# sensorCO2LinearSupply.net
KiCad netlist of a schematic drawn in EAGLE
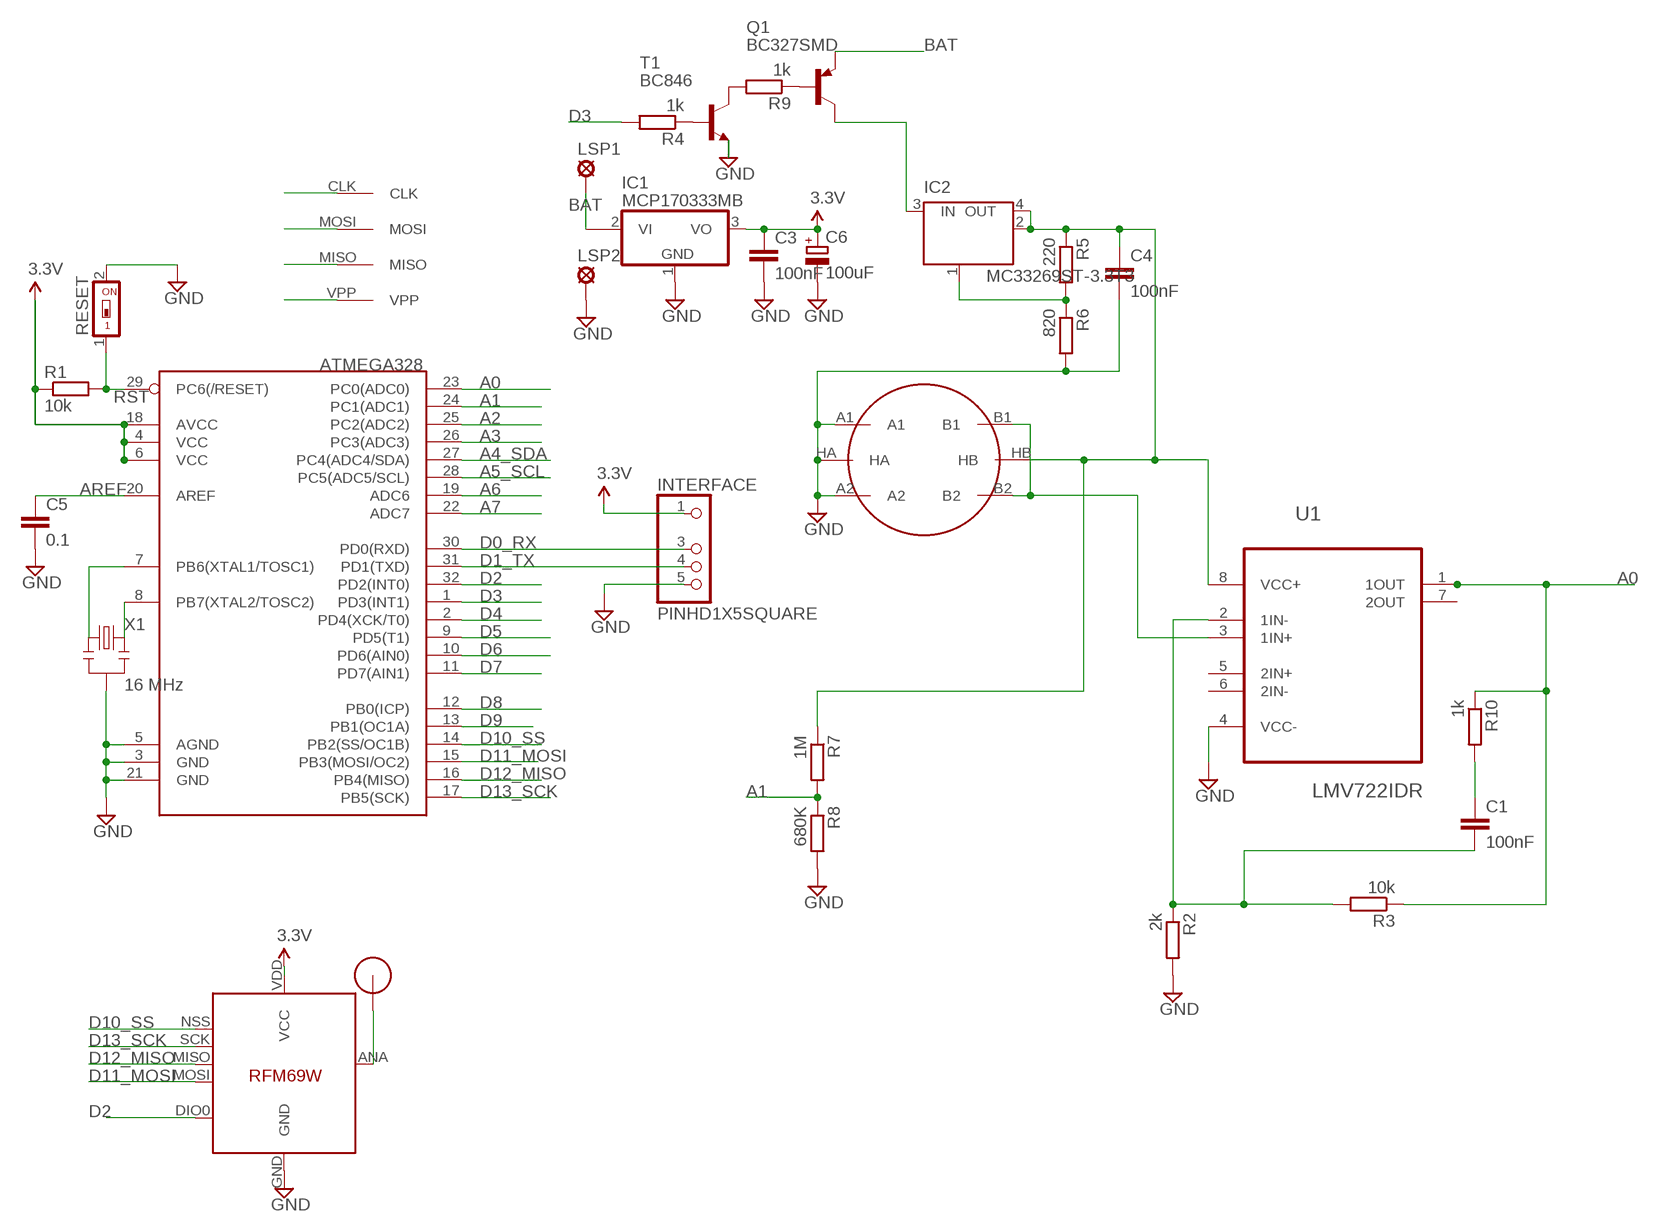
[diagram p0: schematic, sheet 1]

(export (version "E")
  (design (tool "Eeschema 10.0.6"))
  (components
    (comp (ref "ATMEGA328")
      (value "ATMega-328")
      (footprint "eagle-import:TQFP32-08")
      (libsource (lib "eagle-import") (part "ATMEGA168/328TQFP32"))
    )
    (comp (ref "C1")
      (value "100nF")
      (footprint "eagle-import:C2012")
      (libsource (lib "eagle-import") (part "C-EUC2012"))
    )
    (comp (ref "C3")
      (value "100nF")
      (footprint "eagle-import:C2012")
      (libsource (lib "eagle-import") (part "C-EUC2012"))
    )
    (comp (ref "C4")
      (value "100nF")
      (footprint "eagle-import:C2012")
      (libsource (lib "eagle-import") (part "C-EUC2012"))
    )
    (comp (ref "C5")
      (value "0.1")
      (footprint "eagle-import:C2012")
      (libsource (lib "eagle-import") (part "C-EUC2012"))
    )
    (comp (ref "C6")
      (value "100uF")
      (footprint "eagle-import:SMC_B")
      (libsource (lib "eagle-import") (part "CPOL-EUSMCB"))
    )
    (comp (ref "IC1")
      (value "MCP170333MB")
      (footprint "eagle-import:SOT89")
      (libsource (lib "eagle-import") (part "MCP1703MB33"))
    )
    (comp (ref "IC2")
      (value "MC33269ST-3.3T3")
      (footprint "eagle-import:SOT223")
      (libsource (lib "eagle-import") (part "MC33269ST-3.3T3"))
    )
    (comp (ref "IC4")
      (value "RFM69")
      (footprint "eagle-import:RFM69W-MINPADS")
      (libsource (lib "eagle-import") (part "RFM69"))
    )
    (comp (ref "INTERFACE")
      (value "PINHD1X5SQUARE")
      (footprint "eagle-import:PINHD1X05-SQUARE")
      (libsource (lib "eagle-import") (part "PINHD1X5SQUARE"))
    )
    (comp (ref "LSP1")
      (value "LSP11")
      (footprint "eagle-import:LSP11")
      (libsource (lib "eagle-import") (part "LSP11"))
    )
    (comp (ref "LSP2")
      (value "LSP11")
      (footprint "eagle-import:LSP11")
      (libsource (lib "eagle-import") (part "LSP11"))
    )
    (comp (ref "Q1")
      (value "BC327SMD")
      (footprint "eagle-import:SOT23-BEC")
      (libsource (lib "eagle-import") (part "BC327SMD"))
    )
    (comp (ref "R1")
      (value "10k")
      (footprint "eagle-import:R2012")
      (libsource (lib "eagle-import") (part "R-EU_R2012"))
    )
    (comp (ref "R2")
      (value "2k")
      (footprint "eagle-import:R2012")
      (libsource (lib "eagle-import") (part "R-EU_R2012"))
    )
    (comp (ref "R3")
      (value "10k")
      (footprint "eagle-import:R2012")
      (libsource (lib "eagle-import") (part "R-EU_R2012"))
    )
    (comp (ref "R4")
      (value "1k")
      (footprint "eagle-import:R2012")
      (libsource (lib "eagle-import") (part "R-EU_R2012"))
    )
    (comp (ref "R5")
      (value "220")
      (footprint "eagle-import:R2012")
      (libsource (lib "eagle-import") (part "R-EU_R2012"))
    )
    (comp (ref "R6")
      (value "820")
      (footprint "eagle-import:R2012")
      (libsource (lib "eagle-import") (part "R-EU_R2012"))
    )
    (comp (ref "R7")
      (value "1M")
      (footprint "eagle-import:R2012")
      (libsource (lib "eagle-import") (part "R-EU_R2012"))
    )
    (comp (ref "R8")
      (value "680K")
      (footprint "eagle-import:R2012")
      (libsource (lib "eagle-import") (part "R-EU_R2012"))
    )
    (comp (ref "R9")
      (value "1k")
      (footprint "eagle-import:R2012")
      (libsource (lib "eagle-import") (part "R-EU_R2012"))
    )
    (comp (ref "R10")
      (value "1k")
      (footprint "eagle-import:R2012")
      (libsource (lib "eagle-import") (part "R-EU_R2012"))
    )
    (comp (ref "RESET")
      (value "SWS001")
      (footprint "eagle-import:SMS-001")
      (libsource (lib "eagle-import") (part "SWS001"))
    )
    (comp (ref "T1")
      (value "BC846")
      (footprint "eagle-import:SOT23")
      (libsource (lib "eagle-import") (part "BC846"))
    )
    (comp (ref "U$1")
      (value "RFM12B_ANTENNA")
      (footprint "eagle-import:RFM12B-ANTENNA")
      (libsource (lib "eagle-import") (part "RFM12B_ANTENNA"))
    )
    (comp (ref "U$2")
      (value "AVRHEADERDIP")
      (footprint "eagle-import:AVRHEADER")
      (libsource (lib "eagle-import") (part "AVRHEADERDIP"))
    )
    (comp (ref "U$4")
      (value "METHANE_SENSOR")
      (footprint "eagle-import:MQ-3")
      (libsource (lib "eagle-import") (part "METHANE_SENSOR"))
    )
    (comp (ref "U1")
      (value "LMV722IDR")
      (footprint "eagle-import:SOIC127P600X175-8N")
      (libsource (lib "eagle-import") (part "LMV722IDR"))
    )
    (comp (ref "X1")
      (value "16 MHz")
      (footprint "eagle-import:RESONATOR-SMD")
      (libsource (lib "eagle-import") (part "RESONATORSMD"))
    )
  )
  (nets
    (net (code "1") (name "/A0") (class "Default")
      (node (ref "ATMEGA328") (pin "23") (pinfunction "PC0(ADC0)_23") (pintype "bidirectional"))
      (node (ref "R10") (pin "1") (pinfunction "1_1") (pintype "passive"))
      (node (ref "R3") (pin "1") (pinfunction "1_1") (pintype "passive"))
      (node (ref "U1") (pin "1") (pinfunction "1OUT_1") (pintype "output"))
    )
    (net (code "2") (name "/A1") (class "Default")
      (node (ref "ATMEGA328") (pin "24") (pinfunction "PC1(ADC1)_24") (pintype "bidirectional"))
      (node (ref "R7") (pin "2") (pinfunction "2_2") (pintype "passive"))
      (node (ref "R8") (pin "1") (pinfunction "1_1") (pintype "passive"))
    )
    (net (code "3") (name "/A2") (class "Default")
      (node (ref "ATMEGA328") (pin "25") (pinfunction "PC2(ADC2)_25") (pintype "bidirectional"))
    )
    (net (code "4") (name "/A3") (class "Default")
      (node (ref "ATMEGA328") (pin "26") (pinfunction "PC3(ADC3)_26") (pintype "bidirectional"))
    )
    (net (code "5") (name "/A4_SDA") (class "Default")
      (node (ref "ATMEGA328") (pin "27") (pinfunction "PC4(ADC4/SDA)_27") (pintype "bidirectional"))
    )
    (net (code "6") (name "/A5_SCL") (class "Default")
      (node (ref "ATMEGA328") (pin "28") (pinfunction "PC5(ADC5/SCL)_28") (pintype "bidirectional"))
    )
    (net (code "7") (name "/A6") (class "Default")
      (node (ref "ATMEGA328") (pin "19") (pinfunction "ADC6_19") (pintype "bidirectional"))
    )
    (net (code "8") (name "/A7") (class "Default")
      (node (ref "ATMEGA328") (pin "22") (pinfunction "ADC7_22") (pintype "bidirectional"))
    )
    (net (code "9") (name "/AREF") (class "Default")
      (node (ref "ATMEGA328") (pin "20") (pinfunction "AREF_20") (pintype "bidirectional"))
      (node (ref "C5") (pin "1") (pinfunction "1_1") (pintype "passive"))
    )
    (net (code "10") (name "/BAT") (class "Default")
      (node (ref "IC1") (pin "2@1") (pinfunction "VI1_2@1") (pintype "input"))
      (node (ref "LSP1") (pin "MP") (pinfunction "MP_MP") (pintype "passive"))
      (node (ref "Q1") (pin "E") (pinfunction "E_E") (pintype "passive"))
    )
    (net (code "11") (name "/D0_RX") (class "Default")
      (node (ref "ATMEGA328") (pin "30") (pinfunction "PD0(RXD)_30") (pintype "bidirectional"))
      (node (ref "INTERFACE") (pin "3") (pinfunction "3_3") (pintype "passive"))
    )
    (net (code "12") (name "/D1_TX") (class "Default")
      (node (ref "ATMEGA328") (pin "31") (pinfunction "PD1(TXD)_31") (pintype "bidirectional"))
      (node (ref "INTERFACE") (pin "4") (pinfunction "4_4") (pintype "passive"))
    )
    (net (code "13") (name "/D2") (class "Default")
      (node (ref "ATMEGA328") (pin "32") (pinfunction "PD2(INT0)_32") (pintype "bidirectional"))
      (node (ref "IC4") (pin "DIO0") (pinfunction "DIO0_DIO0") (pintype "open_collector"))
    )
    (net (code "14") (name "/D3") (class "Default")
      (node (ref "ATMEGA328") (pin "1") (pinfunction "PD3(INT1)_1") (pintype "bidirectional"))
      (node (ref "R4") (pin "2") (pinfunction "2_2") (pintype "passive"))
    )
    (net (code "15") (name "/D4") (class "Default")
      (node (ref "ATMEGA328") (pin "2") (pinfunction "PD4(XCK/T0)_2") (pintype "bidirectional"))
    )
    (net (code "16") (name "/D5") (class "Default")
      (node (ref "ATMEGA328") (pin "9") (pinfunction "PD5(T1)_9") (pintype "bidirectional"))
    )
    (net (code "17") (name "/D6") (class "Default")
      (node (ref "ATMEGA328") (pin "10") (pinfunction "PD6(AIN0)_10") (pintype "bidirectional"))
    )
    (net (code "18") (name "/D7") (class "Default")
      (node (ref "ATMEGA328") (pin "11") (pinfunction "PD7(AIN1)_11") (pintype "bidirectional"))
    )
    (net (code "19") (name "/D8") (class "Default")
      (node (ref "ATMEGA328") (pin "12") (pinfunction "PB0(ICP)_12") (pintype "bidirectional"))
    )
    (net (code "20") (name "/D9") (class "Default")
      (node (ref "ATMEGA328") (pin "13") (pinfunction "PB1(OC1A)_13") (pintype "bidirectional"))
    )
    (net (code "21") (name "/D10_SS") (class "Default")
      (node (ref "ATMEGA328") (pin "14") (pinfunction "PB2(SS/OC1B)_14") (pintype "bidirectional"))
      (node (ref "IC4") (pin "NSS") (pinfunction "SEL_NSS") (pintype "input"))
    )
    (net (code "22") (name "/D11_MOSI") (class "Default")
      (node (ref "ATMEGA328") (pin "15") (pinfunction "PB3(MOSI/OC2)_15") (pintype "bidirectional"))
      (node (ref "IC4") (pin "MOSI") (pinfunction "MOSI_MOSI") (pintype "output"))
      (node (ref "U$2") (pin "MOSI") (pinfunction "MOSI_MOSI") (pintype "bidirectional"))
    )
    (net (code "23") (name "/D12_MISO") (class "Default")
      (node (ref "ATMEGA328") (pin "16") (pinfunction "PB4(MISO)_16") (pintype "bidirectional"))
      (node (ref "IC4") (pin "MISO") (pinfunction "MISO_MISO") (pintype "input"))
      (node (ref "U$2") (pin "MISO") (pinfunction "MISO_MISO") (pintype "bidirectional"))
    )
    (net (code "24") (name "/D13_SCK") (class "Default")
      (node (ref "ATMEGA328") (pin "17") (pinfunction "PB5(SCK)_17") (pintype "bidirectional"))
      (node (ref "IC4") (pin "SCK") (pinfunction "SCK_SCK") (pintype "input"))
      (node (ref "U$2") (pin "CLK") (pinfunction "CLK_CLK") (pintype "bidirectional"))
    )
    (net (code "25") (name "/RST") (class "Default")
      (node (ref "ATMEGA328") (pin "29") (pinfunction "PC6(/RESET)_29") (pintype "bidirectional"))
      (node (ref "R1") (pin "2") (pinfunction "2_2") (pintype "passive"))
      (node (ref "RESET") (pin "1") (pinfunction "1_1") (pintype "passive"))
      (node (ref "U$2") (pin "VPP") (pinfunction "VPP_VPP") (pintype "bidirectional"))
    )
    (net (code "26") (name "3.3V") (class "Default")
      (node (ref "ATMEGA328") (pin "18") (pinfunction "AVCC_18") (pintype "bidirectional"))
      (node (ref "ATMEGA328") (pin "4") (pinfunction "VCC_4") (pintype "bidirectional"))
      (node (ref "ATMEGA328") (pin "6") (pinfunction "VCC_6") (pintype "bidirectional"))
      (node (ref "C3") (pin "1") (pinfunction "1_1") (pintype "passive"))
      (node (ref "C6") (pin "+") (pinfunction "+_+") (pintype "passive"))
      (node (ref "IC1") (pin "3") (pinfunction "VO_3") (pintype "passive"))
      (node (ref "IC4") (pin "VDD") (pinfunction "VCC_VDD") (pintype "power_in"))
      (node (ref "INTERFACE") (pin "1") (pinfunction "1_1") (pintype "passive"))
      (node (ref "R1") (pin "1") (pinfunction "1_1") (pintype "passive"))
    )
    (net (code "27") (name "GND") (class "Default")
      (node (ref "ATMEGA328") (pin "21") (pinfunction "GND_21") (pintype "bidirectional"))
      (node (ref "ATMEGA328") (pin "3") (pinfunction "GND_3") (pintype "bidirectional"))
      (node (ref "ATMEGA328") (pin "5") (pinfunction "AGND_5") (pintype "bidirectional"))
      (node (ref "C3") (pin "2") (pinfunction "2_2") (pintype "passive"))
      (node (ref "C4") (pin "2") (pinfunction "2_2") (pintype "passive"))
      (node (ref "C5") (pin "2") (pinfunction "2_2") (pintype "passive"))
      (node (ref "C6") (pin "-") (pinfunction "-_-") (pintype "passive"))
      (node (ref "IC1") (pin "1") (pinfunction "GND_1") (pintype "passive"))
      (node (ref "IC4") (pin "GND") (pinfunction "GND_GND") (pintype "power_in"))
      (node (ref "INTERFACE") (pin "5") (pinfunction "5_5") (pintype "passive"))
      (node (ref "LSP2") (pin "MP") (pinfunction "MP_MP") (pintype "passive"))
      (node (ref "R2") (pin "2") (pinfunction "2_2") (pintype "passive"))
      (node (ref "R6") (pin "2") (pinfunction "2_2") (pintype "passive"))
      (node (ref "R8") (pin "2") (pinfunction "2_2") (pintype "passive"))
      (node (ref "RESET") (pin "2") (pinfunction "2_2") (pintype "passive"))
      (node (ref "T1") (pin "2") (pinfunction "E_2") (pintype "passive"))
      (node (ref "U$4") (pin "A1") (pinfunction "A1_A1") (pintype "bidirectional"))
      (node (ref "U$4") (pin "A2") (pinfunction "A2_A2") (pintype "bidirectional"))
      (node (ref "U$4") (pin "HA") (pinfunction "HA_HA") (pintype "bidirectional"))
      (node (ref "U1") (pin "4") (pinfunction "VCC-_4") (pintype "power_in"))
      (node (ref "X1") (pin "2") (pinfunction "2_2") (pintype "passive"))
    )
    (net (code "28") (name "Net-(ATMEGA328-PB6(XTAL1{slash}TOSC1))") (class "Default")
      (node (ref "ATMEGA328") (pin "7") (pinfunction "PB6(XTAL1/TOSC1)_7") (pintype "bidirectional"))
      (node (ref "X1") (pin "1") (pinfunction "1_1") (pintype "passive"))
    )
    (net (code "29") (name "Net-(ATMEGA328-PB7(XTAL2{slash}TOSC2))") (class "Default")
      (node (ref "ATMEGA328") (pin "8") (pinfunction "PB7(XTAL2/TOSC2)_8") (pintype "bidirectional"))
      (node (ref "X1") (pin "3") (pinfunction "3_3") (pintype "passive"))
    )
    (net (code "30") (name "Net-(C1-Pad1)") (class "Default")
      (node (ref "C1") (pin "1") (pinfunction "1_1") (pintype "passive"))
      (node (ref "R10") (pin "2") (pinfunction "2_2") (pintype "passive"))
    )
    (net (code "31") (name "Net-(IC2-GND{slash}ADJ)") (class "Default")
      (node (ref "IC2") (pin "1") (pinfunction "GND/ADJ_1") (pintype "input"))
      (node (ref "R5") (pin "2") (pinfunction "2_2") (pintype "passive"))
      (node (ref "R6") (pin "1") (pinfunction "1_1") (pintype "passive"))
    )
    (net (code "32") (name "Net-(IC2-IN)") (class "Default")
      (node (ref "IC2") (pin "3") (pinfunction "IN_3") (pintype "input"))
      (node (ref "Q1") (pin "C") (pinfunction "C_C") (pintype "passive"))
    )
    (net (code "33") (name "Net-(IC4-ANT)") (class "Default")
      (node (ref "IC4") (pin "ANA") (pinfunction "ANT_ANA") (pintype "passive"))
      (node (ref "U$1") (pin "P$1") (pinfunction "1_P$1") (pintype "bidirectional"))
    )
    (net (code "34") (name "Net-(Q1-PadB)") (class "Default")
      (node (ref "Q1") (pin "B") (pinfunction "B_B") (pintype "passive"))
      (node (ref "R9") (pin "1") (pinfunction "1_1") (pintype "passive"))
    )
    (net (code "35") (name "Net-(T1-B)") (class "Default")
      (node (ref "R4") (pin "1") (pinfunction "1_1") (pintype "passive"))
      (node (ref "T1") (pin "1") (pinfunction "B_1") (pintype "passive"))
    )
    (net (code "36") (name "Net-(T1-C)") (class "Default")
      (node (ref "R9") (pin "2") (pinfunction "2_2") (pintype "passive"))
      (node (ref "T1") (pin "3") (pinfunction "C_3") (pintype "passive"))
    )
    (net (code "37") (name "Net-(U1-1IN+)") (class "Default")
      (node (ref "U$4") (pin "B1") (pinfunction "B1_B1") (pintype "bidirectional"))
      (node (ref "U$4") (pin "B2") (pinfunction "B2_B2") (pintype "bidirectional"))
      (node (ref "U1") (pin "3") (pinfunction "1IN+_3") (pintype "input"))
    )
    (net (code "38") (name "Net-(U1-1IN-)") (class "Default")
      (node (ref "C1") (pin "2") (pinfunction "2_2") (pintype "passive"))
      (node (ref "R2") (pin "1") (pinfunction "1_1") (pintype "passive"))
      (node (ref "R3") (pin "2") (pinfunction "2_2") (pintype "passive"))
      (node (ref "U1") (pin "2") (pinfunction "1IN-_2") (pintype "input"))
    )
    (net (code "39") (name "Net-(U1-VCC+)") (class "Default")
      (node (ref "C4") (pin "1") (pinfunction "1_1") (pintype "passive"))
      (node (ref "IC2") (pin "2") (pinfunction "OUT_2") (pintype "passive"))
      (node (ref "IC2") (pin "4") (pinfunction "OUT_4") (pintype "passive"))
      (node (ref "R5") (pin "1") (pinfunction "1_1") (pintype "passive"))
      (node (ref "R7") (pin "1") (pinfunction "1_1") (pintype "passive"))
      (node (ref "U$4") (pin "HB") (pinfunction "HB_HB") (pintype "bidirectional"))
      (node (ref "U1") (pin "8") (pinfunction "VCC+_8") (pintype "power_in"))
    )
    (net (code "40") (name "unconnected-(IC1-VI-Pad2)") (class "Default")
      (node (ref "IC1") (pin "2") (pinfunction "VI_2") (pintype "input"))
    )
    (net (code "41") (name "unconnected-(U1-2IN+-Pad5)") (class "Default")
      (node (ref "U1") (pin "5") (pinfunction "2IN+_5") (pintype "input"))
    )
    (net (code "42") (name "unconnected-(U1-2IN--Pad6)") (class "Default")
      (node (ref "U1") (pin "6") (pinfunction "2IN-_6") (pintype "input"))
    )
    (net (code "43") (name "unconnected-(U1-2OUT-Pad7)") (class "Default")
      (node (ref "U1") (pin "7") (pinfunction "2OUT_7") (pintype "output"))
    )
  )
)
